# mayfly_peripheral_smd_reva.net
KiCad netlist of a schematic drawn in EAGLE
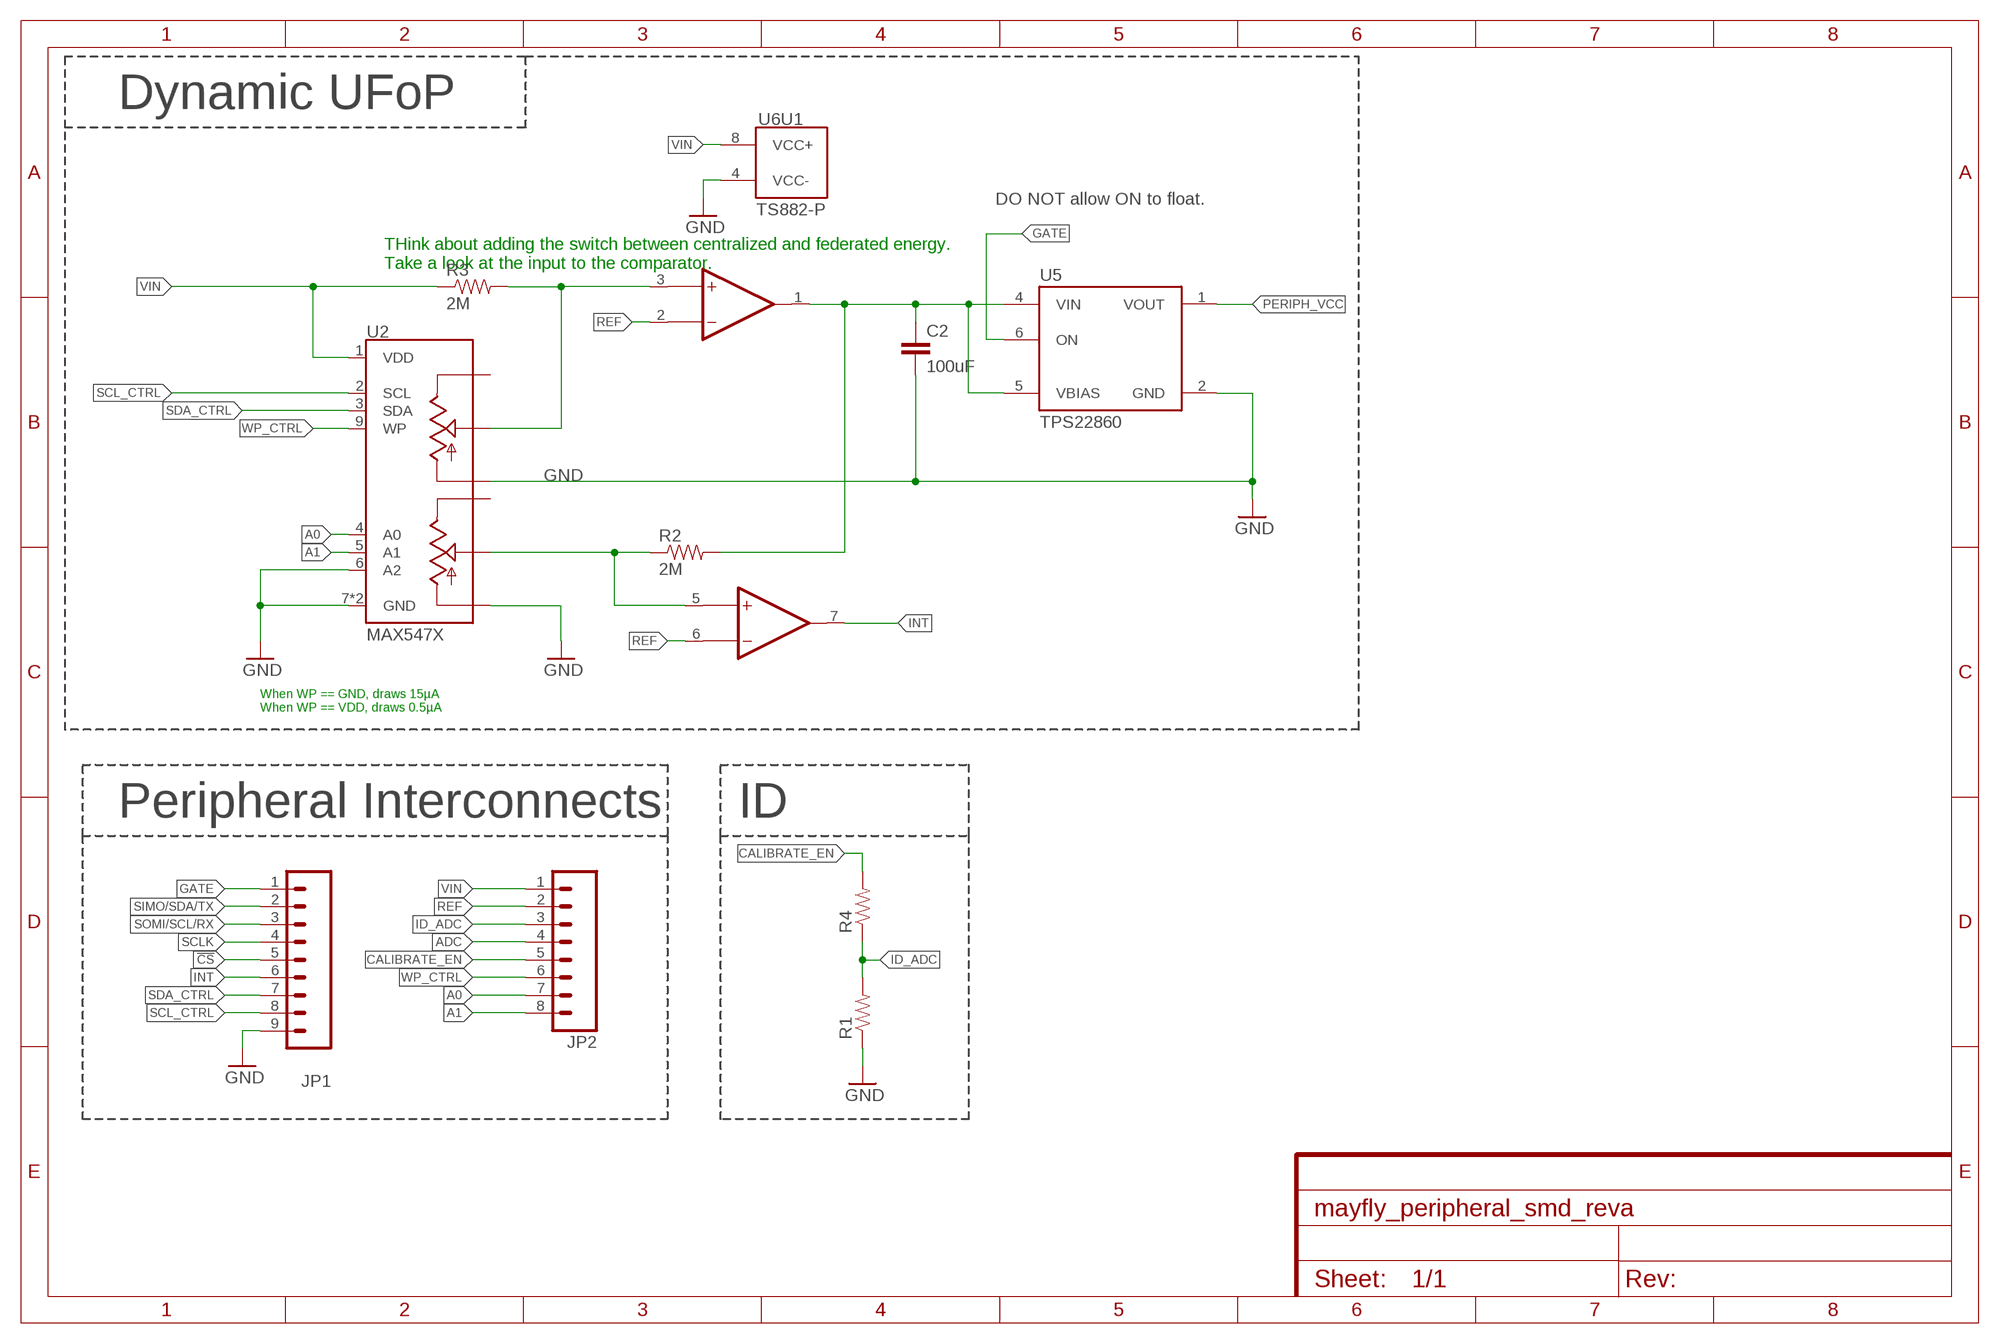
[diagram p0: schematic, sheet 1]

(export (version "E")
  (design (tool "Eeschema 10.0.6"))
  (components
    (comp (ref "C2")
      (value "100uF")
      (footprint "eagle-import:1210")
      (libsource (lib "eagle-import") (part "CAP1210"))
    )
    (comp (ref "JP1")
      (value "M091.27MM")
      (footprint "eagle-import:1X09-1.27MM")
      (libsource (lib "eagle-import") (part "M091.27MM"))
    )
    (comp (ref "JP2")
      (value "M081X08_1.27MM_SMD")
      (footprint "eagle-import:1X08_1.27MM_SMD")
      (libsource (lib "eagle-import") (part "M081X08_1.27MM_SMD"))
    )
    (comp (ref "R1")
      (value "R-EU0603")
      (footprint "eagle-import:0603")
      (libsource (lib "eagle-import") (part "R-EU0603"))
    )
    (comp (ref "R2")
      (value "2M")
      (footprint "eagle-import:0603")
      (libsource (lib "eagle-import") (part "R-EU0603"))
    )
    (comp (ref "R3")
      (value "2M")
      (footprint "eagle-import:0603")
      (libsource (lib "eagle-import") (part "R-EU0603"))
    )
    (comp (ref "R4")
      (value "R-EU0603")
      (footprint "eagle-import:0603")
      (libsource (lib "eagle-import") (part "R-EU0603"))
    )
    (comp (ref "U2")
      (value "MAX547X")
      (footprint "eagle-import:QFN16")
      (libsource (lib "eagle-import") (part "MAX547X"))
    )
    (comp (ref "U5")
      (value "TPS22860")
      (footprint "eagle-import:TSOT23-6")
      (libsource (lib "eagle-import") (part "TPS22860"))
    )
    (comp (ref "U6")
      (value "TS882-P")
      (footprint "eagle-import:UDFN8")
      (fields (field (name "DIGIKEY") "497-14073-1-ND"))
      (libsource (lib "eagle-import") (part "TS882-P"))
    )
  )
  (nets
    (net (code "1") (name "/~{CS}") (class "Default")
      (node (ref "JP1") (pin "5") (pinfunction "5_5") (pintype "passive"))
    )
    (net (code "2") (name "A0") (class "Default")
      (node (ref "JP2") (pin "7") (pinfunction "7_7") (pintype "passive"))
      (node (ref "U2") (pin "4") (pinfunction "A0_4") (pintype "bidirectional"))
    )
    (net (code "3") (name "A1") (class "Default")
      (node (ref "JP2") (pin "8") (pinfunction "8_8") (pintype "passive"))
      (node (ref "U2") (pin "5") (pinfunction "A1_5") (pintype "bidirectional"))
    )
    (net (code "4") (name "ADC") (class "Default")
      (node (ref "JP2") (pin "4") (pinfunction "4_4") (pintype "passive"))
    )
    (net (code "5") (name "CALIBRATE_EN") (class "Default")
      (node (ref "JP2") (pin "5") (pinfunction "5_5") (pintype "passive"))
      (node (ref "R4") (pin "2") (pinfunction "2_2") (pintype "passive"))
    )
    (net (code "6") (name "GATE") (class "Default")
      (node (ref "JP1") (pin "1") (pinfunction "1_1") (pintype "passive"))
      (node (ref "U5") (pin "6") (pinfunction "ON_6") (pintype "bidirectional"))
    )
    (net (code "7") (name "GND") (class "Default")
      (node (ref "C2") (pin "2") (pinfunction "2_2") (pintype "passive"))
      (node (ref "JP1") (pin "9") (pinfunction "9_9") (pintype "passive"))
      (node (ref "R1") (pin "1") (pinfunction "1_1") (pintype "passive"))
      (node (ref "U2") (pin "10") (pinfunction "LB_10") (pintype "bidirectional"))
      (node (ref "U2") (pin "13") (pinfunction "LA_13") (pintype "passive"))
      (node (ref "U2") (pin "6") (pinfunction "A2_6") (pintype "bidirectional"))
      (node (ref "U2") (pin "7") (pinfunction "GND_7") (pintype "bidirectional"))
      (node (ref "U2") (pin "TH") (pinfunction "GND_TH") (pintype "bidirectional"))
      (node (ref "U5") (pin "2") (pinfunction "GND_2") (pintype "bidirectional"))
      (node (ref "U6") (pin "4") (pinfunction "VCC-_4") (pintype "bidirectional"))
    )
    (net (code "8") (name "ID_ADC") (class "Default")
      (node (ref "JP2") (pin "3") (pinfunction "3_3") (pintype "passive"))
      (node (ref "R1") (pin "2") (pinfunction "2_2") (pintype "passive"))
      (node (ref "R4") (pin "1") (pinfunction "1_1") (pintype "passive"))
    )
    (net (code "9") (name "INT") (class "Default")
      (node (ref "JP1") (pin "6") (pinfunction "6_6") (pintype "passive"))
      (node (ref "U6") (pin "7") (pinfunction "OUT1_7") (pintype "output"))
    )
    (net (code "10") (name "Net-(U2-WA)") (class "Default")
      (node (ref "R3") (pin "2") (pinfunction "2_2") (pintype "passive"))
      (node (ref "U2") (pin "14") (pinfunction "WA_14") (pintype "passive"))
      (node (ref "U6") (pin "3") (pinfunction "IN1+_3") (pintype "input"))
    )
    (net (code "11") (name "Net-(U2-WB)") (class "Default")
      (node (ref "R2") (pin "1") (pinfunction "1_1") (pintype "passive"))
      (node (ref "U2") (pin "11") (pinfunction "WB_11") (pintype "bidirectional"))
      (node (ref "U6") (pin "5") (pinfunction "IN1+_5") (pintype "input"))
    )
    (net (code "12") (name "Net-(U5-VBIAS)") (class "Default")
      (node (ref "C2") (pin "1") (pinfunction "1_1") (pintype "passive"))
      (node (ref "R2") (pin "2") (pinfunction "2_2") (pintype "passive"))
      (node (ref "U5") (pin "4") (pinfunction "VIN_4") (pintype "bidirectional"))
      (node (ref "U5") (pin "5") (pinfunction "VBIAS_5") (pintype "bidirectional"))
      (node (ref "U6") (pin "1") (pinfunction "OUT1_1") (pintype "output"))
    )
    (net (code "13") (name "PERIPH_VCC") (class "Default")
      (node (ref "U5") (pin "1") (pinfunction "VOUT_1") (pintype "bidirectional"))
    )
    (net (code "14") (name "REF") (class "Default")
      (node (ref "JP2") (pin "2") (pinfunction "2_2") (pintype "passive"))
      (node (ref "U6") (pin "2") (pinfunction "IN1-_2") (pintype "input"))
      (node (ref "U6") (pin "6") (pinfunction "IN1-_6") (pintype "input"))
    )
    (net (code "15") (name "SCLK") (class "Default")
      (node (ref "JP1") (pin "4") (pinfunction "4_4") (pintype "passive"))
    )
    (net (code "16") (name "SCL_CTRL") (class "Default")
      (node (ref "JP1") (pin "8") (pinfunction "8_8") (pintype "passive"))
      (node (ref "U2") (pin "2") (pinfunction "SCL_2") (pintype "bidirectional"))
    )
    (net (code "17") (name "SDA_CTRL") (class "Default")
      (node (ref "JP1") (pin "7") (pinfunction "7_7") (pintype "passive"))
      (node (ref "U2") (pin "3") (pinfunction "SDA_3") (pintype "bidirectional"))
    )
    (net (code "18") (name "SIMO{slash}SDA{slash}TX") (class "Default")
      (node (ref "JP1") (pin "2") (pinfunction "2_2") (pintype "passive"))
    )
    (net (code "19") (name "SOMI{slash}SCL{slash}RX") (class "Default")
      (node (ref "JP1") (pin "3") (pinfunction "3_3") (pintype "passive"))
    )
    (net (code "20") (name "VIN") (class "Default")
      (node (ref "JP2") (pin "1") (pinfunction "1_1") (pintype "passive"))
      (node (ref "R3") (pin "1") (pinfunction "1_1") (pintype "passive"))
      (node (ref "U2") (pin "1") (pinfunction "VDD_1") (pintype "bidirectional"))
      (node (ref "U6") (pin "8") (pinfunction "VCC+_8") (pintype "bidirectional"))
    )
    (net (code "21") (name "WP_CTRL") (class "Default")
      (node (ref "JP2") (pin "6") (pinfunction "6_6") (pintype "passive"))
      (node (ref "U2") (pin "9") (pinfunction "WP_9") (pintype "bidirectional"))
    )
    (net (code "22") (name "unconnected-(U2-HA-Pad15)") (class "Default")
      (node (ref "U2") (pin "15") (pinfunction "HA_15") (pintype "passive"))
    )
    (net (code "23") (name "unconnected-(U2-HB-Pad12)") (class "Default")
      (node (ref "U2") (pin "12") (pinfunction "HB_12") (pintype "bidirectional"))
    )
  )
)
